# Buck-Schematic.net
KiCad netlist of a schematic drawn in Altium Designer
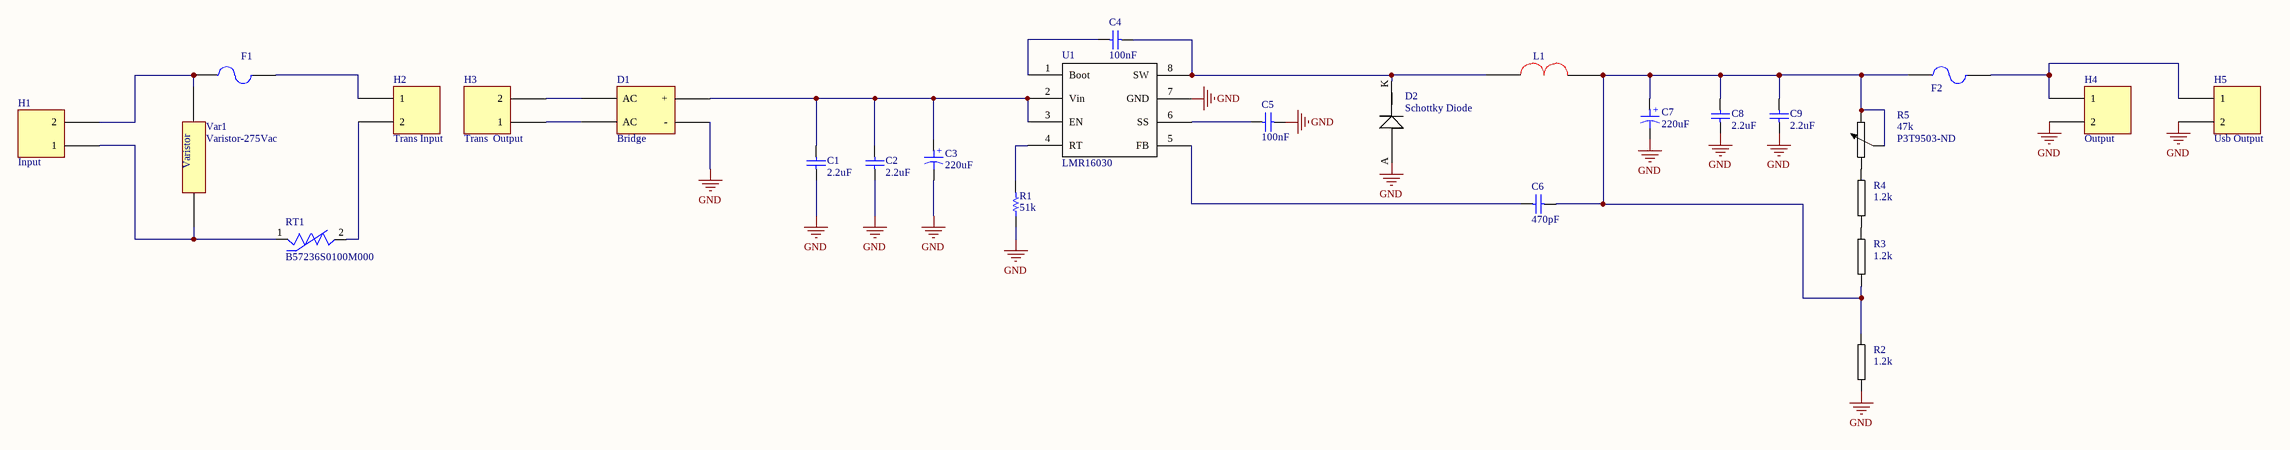
[diagram p0: Buck-Schematic.SchDoc]

(export (version "E")
  (design (tool "Eeschema 10.0.6"))
  (components
    (comp (ref "C1")
      (value "2.2uF")
      (footprint "CAPC3413X12N")
      (description "CAP 0805")
      (fields (field (name "DESIGNER") "Abbas Basereh"))
      (libsource (lib "Altium") (part "CAP SMD 0805"))
    )
    (comp (ref "C2")
      (value "2.2uF")
      (footprint "CAPC3413X12N")
      (description "CAP 0805")
      (fields (field (name "DESIGNER") "Abbas Basereh"))
      (libsource (lib "Altium") (part "CAP SMD 0805"))
    )
    (comp (ref "C3")
      (value "220uF")
      (footprint "CAP SMD 470uF")
      (description "Cap electrolitic radial")
      (fields (field (name "DESIGNER") "Abbas Basereh"))
      (libsource (lib "Altium") (part "Cap ELECTROLITIC TOTAL SIZE"))
    )
    (comp (ref "C4")
      (value "100nF")
      (footprint "CAP0603")
      (description "TOTAL CAPACITOR SMD PACK")
      (fields (field (name "DESIGNER") "Abbas Basereh"))
      (libsource (lib "Altium") (part "CAP SMD PACKAGE"))
    )
    (comp (ref "C5")
      (value "100nF")
      (footprint "CAP0603")
      (description "TOTAL CAPACITOR SMD PACK")
      (fields (field (name "DESIGNER") "Abbas Basereh"))
      (libsource (lib "Altium") (part "CAP SMD PACKAGE"))
    )
    (comp (ref "C6")
      (value "470pF")
      (footprint "CAP0603")
      (description "TOTAL CAPACITOR SMD PACK")
      (fields (field (name "DESIGNER") "Abbas Basereh"))
      (libsource (lib "Altium") (part "CAP SMD PACKAGE"))
    )
    (comp (ref "C7")
      (value "220uF")
      (footprint "CAP SMD 470uF")
      (description "Cap electrolitic radial")
      (fields (field (name "DESIGNER") "Abbas Basereh"))
      (libsource (lib "Altium") (part "Cap ELECTROLITIC TOTAL SIZE"))
    )
    (comp (ref "C8")
      (value "2.2uF")
      (footprint "CAPC3413X12N")
      (description "CAP 0805")
      (fields (field (name "DESIGNER") "Abbas Basereh"))
      (libsource (lib "Altium") (part "CAP SMD 0805"))
    )
    (comp (ref "C9")
      (value "2.2uF")
      (footprint "CAPC3413X12N")
      (description "CAP 0805")
      (fields (field (name "DESIGNER") "Abbas Basereh"))
      (libsource (lib "Altium") (part "CAP SMD 0805"))
    )
    (comp (ref "D1")
      (value "Bridge")
      (footprint "PCBComponent_1")
      (libsource (lib "BUCK-PROJECT") (part "Bridge"))
    )
    (comp (ref "D2")
      (value "Schottky Diode")
      (footprint "Schottky Diode")
      (libsource (lib "BUCK-PROJECT") (part "Schottky Diode"))
    )
    (comp (ref "F1")
      (value "F=1.0 A")
      (footprint "Fuse 5x20 With holder pin")
      (description "Fuses 5x20")
      (fields (field (name "DESIGNER") "Abbas Basereh"))
      (libsource (lib "Altium") (part "Fuse 5x20 with holdeer pins"))
    )
    (comp (ref "F2")
      (value "F=1.0 A")
      (footprint "1206 FUSE")
      (description "SMD Fuses 1206")
      (fields (field (name "DESIGNER") "Abbas Basereh"))
      (libsource (lib "Altium") (part "Fuse SMD1206"))
    )
    (comp (ref "H1") (value "Input") (footprint "Header") (libsource (lib "") (part "Header_1")))
    (comp (ref "H2")
      (value "Trans Input")
      (footprint "Header")
      (libsource (lib "BUCK-PROJECT") (part "Header"))
    )
    (comp (ref "H3") (value "Trans  Output") (footprint "Header") (libsource (lib "") (part "Header_1")))
    (comp (ref "H4") (value "Output") (footprint "Header") (libsource (lib "BUCK-PROJECT") (part "Header")))
    (comp (ref "H5")
      (value "Usb Output")
      (footprint "Header")
      (libsource (lib "BUCK-PROJECT") (part "Header"))
    )
    (comp (ref "L1")
      (value "Inductor")
      (footprint "Inductor")
      (libsource (lib "BUCK-PROJECT") (part "Inductor"))
    )
    (comp (ref "R1")
      (value "51k")
      (footprint "RESC3413X04N")
      (description "RES 0805")
      (fields (field (name "DESIGNER") "Abbas Basereh"))
      (libsource (lib "Altium") (part "RES 0805 0.125W"))
    )
    (comp (ref "R2")
      (value "1.2k")
      (footprint "0805R-82K")
      (description "RESISTOR 0805 1/4 WATT THIN FILM")
      (libsource (lib "vh_altium_library") (part "0805R-82"))
    )
    (comp (ref "R3")
      (value "1.2k")
      (footprint "0805R-82K")
      (description "RESISTOR 0805 1/4 WATT THIN FILM")
      (libsource (lib "vh_altium_library") (part "0805R-82"))
    )
    (comp (ref "R4")
      (value "1.2k")
      (footprint "0805R-82K")
      (description "RESISTOR 0805 1/4 WATT THIN FILM")
      (libsource (lib "vh_altium_library") (part "0805R-82"))
    )
    (comp (ref "R5")
      (value "47k")
      (footprint "pot-pana-evue")
      (description "Adjustable resistor")
      (fields (field (name "SUPPLIER PART NUMBER 1") "P3T9503-ND"))
      (libsource (lib "vh_altium_library") (part "THPOT-PANA-EVUE-50K"))
    )
    (comp (ref "RT1")
      (value "B57236S0100M000")
      (footprint "THRMRB500W60L1150T500H1600")
      (description "Thermistor NTC 10 Ohm 20% 2-Pin Radial 2900K Bulk Automotive")
      (fields (field (name "MF") "EPCOS"))
      (libsource (lib "B57236S0100M000") (part "B57236S0100M000"))
    )
    (comp (ref "U1")
      (value "LMR16030")
      (footprint "LMR16030")
      (libsource (lib "BUCK-PROJECT") (part "LMR16030"))
    )
    (comp (ref "Var1")
      (value "Varistor-275Vac")
      (footprint "Varistor - duplicate1")
      (libsource (lib "Varistor-275Vac") (part "Varistor-275Vac"))
    )
  )
  (nets
    (net (code "1") (name "GND") (class "Default")
      (node (ref "C1") (pin "1") (pinfunction "1_1") (pintype "passive"))
      (node (ref "C2") (pin "1") (pinfunction "1_1") (pintype "passive"))
      (node (ref "C3") (pin "2") (pinfunction "2_2") (pintype "passive"))
      (node (ref "C5") (pin "1") (pinfunction "1_1") (pintype "passive"))
      (node (ref "C7") (pin "2") (pinfunction "2_2") (pintype "passive"))
      (node (ref "C8") (pin "1") (pinfunction "1_1") (pintype "passive"))
      (node (ref "C9") (pin "1") (pinfunction "1_1") (pintype "passive"))
      (node (ref "D1") (pin "1") (pinfunction "-_1") (pintype "passive"))
      (node (ref "D2") (pin "A") (pinfunction "A_A") (pintype "passive"))
      (node (ref "H4") (pin "2") (pinfunction "2_2") (pintype "passive"))
      (node (ref "H5") (pin "2") (pinfunction "2_2") (pintype "passive"))
      (node (ref "R1") (pin "1") (pinfunction "1_1") (pintype "passive"))
      (node (ref "R2") (pin "2") (pintype "passive"))
      (node (ref "U1") (pin "7") (pinfunction "GND_7") (pintype "passive"))
    )
    (net (code "2") (name "Net-(C6-Pad1)") (class "Default")
      (node (ref "C6") (pin "1") (pinfunction "1_1") (pintype "passive"))
      (node (ref "C7") (pin "1") (pinfunction "1_1") (pintype "passive"))
      (node (ref "C8") (pin "2") (pinfunction "2_2") (pintype "passive"))
      (node (ref "C9") (pin "2") (pinfunction "2_2") (pintype "passive"))
      (node (ref "F2") (pin "1") (pinfunction "1_1") (pintype "passive"))
      (node (ref "L1") (pin "2") (pinfunction "2_2") (pintype "passive"))
      (node (ref "R2") (pin "1") (pintype "passive"))
      (node (ref "R3") (pin "2") (pintype "passive"))
      (node (ref "R5") (pin "2") (pinfunction "2_2") (pintype "passive"))
      (node (ref "R5") (pin "W") (pinfunction "W_W") (pintype "passive"))
    )
    (net (code "3") (name "Net-(D1-+)") (class "Default")
      (node (ref "C1") (pin "2") (pinfunction "2_2") (pintype "passive"))
      (node (ref "C2") (pin "2") (pinfunction "2_2") (pintype "passive"))
      (node (ref "C3") (pin "1") (pinfunction "1_1") (pintype "passive"))
      (node (ref "D1") (pin "4") (pinfunction "+_4") (pintype "passive"))
      (node (ref "U1") (pin "2") (pinfunction "Vin_2") (pintype "passive"))
      (node (ref "U1") (pin "3") (pinfunction "EN_3") (pintype "passive"))
    )
    (net (code "4") (name "Net-(D1-AC-Pad2)") (class "Default")
      (node (ref "D1") (pin "2") (pinfunction "AC_2") (pintype "passive"))
      (node (ref "H3") (pin "1") (pinfunction "1_1") (pintype "passive"))
    )
    (net (code "5") (name "Net-(D1-AC-Pad3)") (class "Default")
      (node (ref "D1") (pin "3") (pinfunction "AC_3") (pintype "passive"))
      (node (ref "H3") (pin "2") (pinfunction "2_2") (pintype "passive"))
    )
    (net (code "6") (name "Net-(F1-Pad1)") (class "Default")
      (node (ref "F1") (pin "1") (pinfunction "1_1") (pintype "passive"))
      (node (ref "H1") (pin "2") (pinfunction "2_2") (pintype "passive"))
      (node (ref "Var1") (pin "2") (pinfunction "2_2") (pintype "passive"))
    )
    (net (code "7") (name "Net-(F1-Pad2)") (class "Default")
      (node (ref "F1") (pin "2") (pinfunction "2_2") (pintype "passive"))
      (node (ref "H2") (pin "1") (pinfunction "1_1") (pintype "passive"))
    )
    (net (code "8") (name "Net-(F2-Pad2)") (class "Default")
      (node (ref "F2") (pin "2") (pinfunction "2_2") (pintype "passive"))
      (node (ref "H4") (pin "1") (pinfunction "1_1") (pintype "passive"))
      (node (ref "H5") (pin "1") (pinfunction "1_1") (pintype "passive"))
    )
    (net (code "9") (name "Net-(H1-Pad1)") (class "Default")
      (node (ref "H1") (pin "1") (pinfunction "1_1") (pintype "passive"))
      (node (ref "RT1") (pin "1") (pinfunction "1_1") (pintype "passive"))
      (node (ref "Var1") (pin "1") (pinfunction "1_1") (pintype "passive"))
    )
    (net (code "10") (name "Net-(H2-Pad2)") (class "Default")
      (node (ref "H2") (pin "2") (pinfunction "2_2") (pintype "passive"))
      (node (ref "RT1") (pin "2") (pinfunction "2_2") (pintype "passive"))
    )
    (net (code "11") (name "Net-(R3-Pad1)") (class "Default")
      (node (ref "R3") (pin "1") (pintype "passive"))
      (node (ref "R4") (pin "2") (pintype "passive"))
    )
    (net (code "12") (name "Net-(R4-Pad1)") (class "Default")
      (node (ref "R4") (pin "1") (pintype "passive"))
      (node (ref "R5") (pin "1") (pinfunction "1_1") (pintype "passive"))
    )
    (net (code "13") (name "Net-(U1-Boot)") (class "Default")
      (node (ref "C4") (pin "2") (pinfunction "2_2") (pintype "passive"))
      (node (ref "U1") (pin "1") (pinfunction "Boot_1") (pintype "passive"))
    )
    (net (code "14") (name "Net-(U1-FB)") (class "Default")
      (node (ref "C6") (pin "2") (pinfunction "2_2") (pintype "passive"))
      (node (ref "U1") (pin "5") (pinfunction "FB_5") (pintype "passive"))
    )
    (net (code "15") (name "Net-(U1-RT)") (class "Default")
      (node (ref "R1") (pin "2") (pinfunction "2_2") (pintype "passive"))
      (node (ref "U1") (pin "4") (pinfunction "RT_4") (pintype "passive"))
    )
    (net (code "16") (name "Net-(U1-SS)") (class "Default")
      (node (ref "C5") (pin "2") (pinfunction "2_2") (pintype "passive"))
      (node (ref "U1") (pin "6") (pinfunction "SS_6") (pintype "passive"))
    )
    (net (code "17") (name "Net-(U1-SW)") (class "Default")
      (node (ref "C4") (pin "1") (pinfunction "1_1") (pintype "passive"))
      (node (ref "D2") (pin "K") (pinfunction "K_K") (pintype "passive"))
      (node (ref "L1") (pin "1") (pinfunction "1_1") (pintype "passive"))
      (node (ref "U1") (pin "8") (pinfunction "SW_8") (pintype "passive"))
    )
  )
)
